# Power.net
KiCad netlist of a schematic drawn in Altium Designer
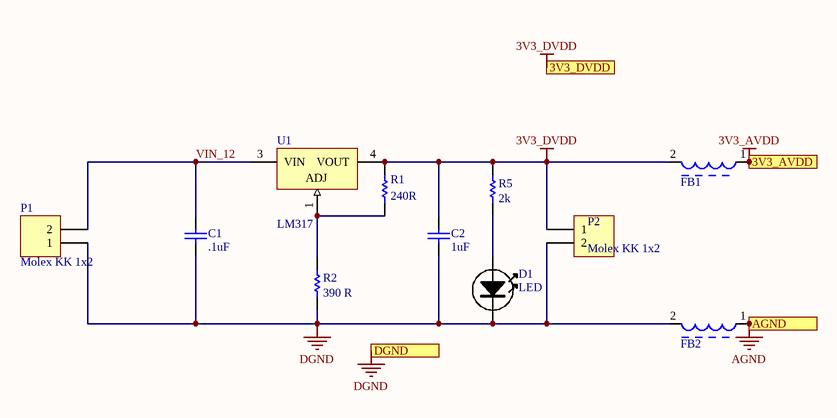
[diagram p0: Power.SchDoc]

(export (version "E")
  (design (tool "Eeschema 10.0.6"))
  (components
    (comp (ref "C1")
      (value ".1uF")
      (footprint "C0805")
      (description "0805 Capacitor")
      (libsource (lib "PARSEC") (part "C0805"))
    )
    (comp (ref "C2")
      (value "1uF")
      (footprint "C0805")
      (description "0805 Capacitor")
      (libsource (lib "PARSEC") (part "C0805"))
    )
    (comp (ref "D1")
      (value "LED")
      (footprint "0805LED")
      (fields
        (field (name "MANUFACTURER") "OSRAM Opto Semiconductors Inc")
        (field (name "MANUFACTURER PART NUMBER") "LS T676-Q1R2-1-Z")
      )
      (libsource (lib "PARSEC") (part "LED"))
    )
    (comp (ref "FB1")
      (value "FERRITE")
      (footprint "R0805")
      (description "FERRITE BEAD 0805")
      (libsource (lib "PARSEC1") (part "FERRITE"))
    )
    (comp (ref "FB2")
      (value "FERRITE")
      (footprint "R0805")
      (description "FERRITE BEAD 0805")
      (libsource (lib "PARSEC1") (part "FERRITE"))
    )
    (comp (ref "P1")
      (value "Molex KK 1x2")
      (footprint "Molex KK 2x1")
      (description "1x2 Molex KK Connector")
      (libsource (lib "") (part "Molex KK 1x2_1"))
    )
    (comp (ref "P2")
      (value "Molex KK 1x2")
      (footprint "Molex KK 2x1")
      (description "1x2 Molex KK Connector")
      (libsource (lib "*") (part "Molex KK 1x2"))
    )
    (comp (ref "R1")
      (value "240R")
      (footprint "R0805")
      (description "RESISTOR 0805")
      (libsource (lib "*") (part "R0805"))
    )
    (comp (ref "R2")
      (value "390 R")
      (footprint "R0805")
      (description "RESISTOR 0805")
      (libsource (lib "*") (part "R0805"))
    )
    (comp (ref "R5")
      (value "2k")
      (footprint "R0805")
      (description "RESISTOR 0805")
      (libsource (lib "*") (part "R0805"))
    )
    (comp (ref "U1")
      (value "LM317")
      (footprint "D-PAK")
      (description "Linear Voltage Regulator")
      (libsource (lib "Copy of PARSEC") (part "LM317"))
    )
  )
  (nets
    (net (code "1") (name "/VIN_12") (class "Default")
      (node (ref "C1") (pin "1") (pinfunction "1_1") (pintype "passive"))
      (node (ref "P1") (pin "2") (pinfunction "2_2") (pintype "passive"))
      (node (ref "U1") (pin "3") (pinfunction "VIN_3") (pintype "power_in"))
    )
    (net (code "2") (name "3V3_AVDD") (class "Default")
      (node (ref "FB1") (pin "1") (pinfunction "1_1") (pintype "passive"))
    )
    (net (code "3") (name "3V3_DVDD") (class "Default")
      (node (ref "C2") (pin "1") (pinfunction "1_1") (pintype "passive"))
      (node (ref "FB1") (pin "2") (pinfunction "2_2") (pintype "passive"))
      (node (ref "P2") (pin "1") (pinfunction "1_1") (pintype "passive"))
      (node (ref "R1") (pin "2") (pinfunction "2_2") (pintype "passive"))
      (node (ref "R5") (pin "2") (pinfunction "2_2") (pintype "passive"))
      (node (ref "U1") (pin "4") (pinfunction "VOUT_4") (pintype "power_in"))
    )
    (net (code "4") (name "AGND") (class "Default")
      (node (ref "FB2") (pin "1") (pinfunction "1_1") (pintype "passive"))
    )
    (net (code "5") (name "DGND") (class "Default")
      (node (ref "C1") (pin "2") (pinfunction "2_2") (pintype "passive"))
      (node (ref "C2") (pin "2") (pinfunction "2_2") (pintype "passive"))
      (node (ref "D1") (pin "K") (pintype "passive"))
      (node (ref "FB2") (pin "2") (pinfunction "2_2") (pintype "passive"))
      (node (ref "P1") (pin "1") (pinfunction "1_1") (pintype "passive"))
      (node (ref "P2") (pin "2") (pinfunction "2_2") (pintype "passive"))
      (node (ref "R2") (pin "1") (pinfunction "1_1") (pintype "passive"))
    )
    (net (code "6") (name "Net-(D1-PadA)") (class "Default")
      (node (ref "D1") (pin "A") (pintype "passive"))
      (node (ref "R5") (pin "1") (pinfunction "1_1") (pintype "passive"))
    )
    (net (code "7") (name "Net-(U1-ADJ)") (class "Default")
      (node (ref "R1") (pin "1") (pinfunction "1_1") (pintype "passive"))
      (node (ref "R2") (pin "2") (pinfunction "2_2") (pintype "passive"))
      (node (ref "U1") (pin "1") (pinfunction "ADJ_1") (pintype "input"))
    )
  )
)
